# MCU.net
KiCad netlist of a schematic drawn in Altium Designer
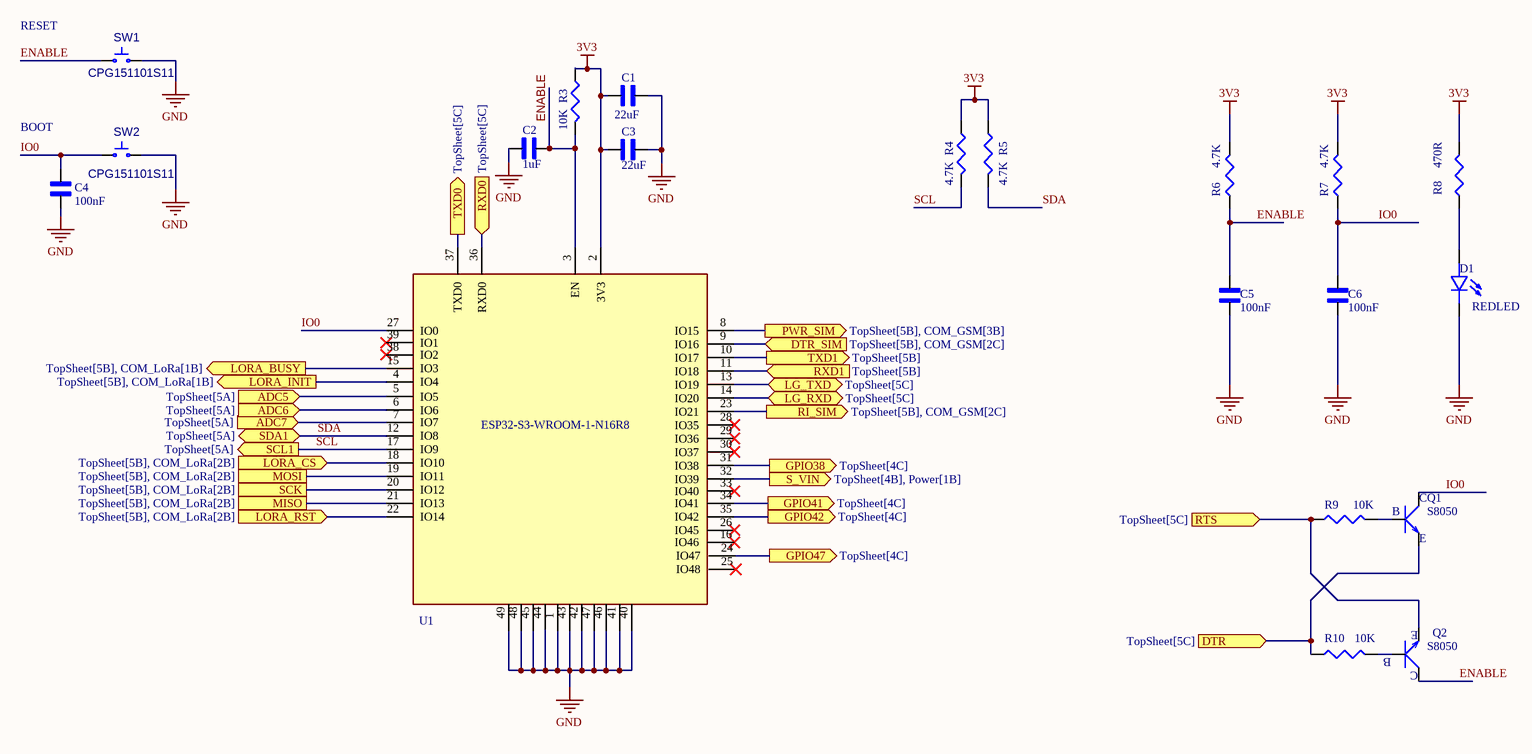
[diagram p0: MCU.SchDoc]

(export (version "E")
  (design (tool "Eeschema 10.0.6"))
  (components
    (comp (ref "C1")
      (value "22uF")
      (footprint "C0603")
      (fields (field (name "MF") "Murata") (field (name "MP") "GJM1555C1HR10BB01J"))
      (libsource (lib "") (part "Capacitor non polar_1"))
    )
    (comp (ref "C2")
      (value "1uF")
      (footprint "C0603")
      (fields (field (name "MF") "Murata") (field (name "MP") "GJM1555C1HR10BB01J"))
      (libsource (lib "") (part "Capacitor non polar_1"))
    )
    (comp (ref "C3")
      (value "22uF")
      (footprint "C0603")
      (fields (field (name "MF") "Murata") (field (name "MP") "GJM1555C1HR10BB01J"))
      (libsource (lib "") (part "Capacitor non polar_1"))
    )
    (comp (ref "C4")
      (value "100nF")
      (footprint "C0603")
      (fields (field (name "MF") "Murata") (field (name "MP") "GJM1555C1HR10BB01J"))
      (libsource (lib "") (part "Capacitor non polar_2"))
    )
    (comp (ref "C5")
      (value "100nF")
      (footprint "C0603")
      (fields (field (name "MF") "Murata") (field (name "MP") "GJM1555C1HR10BB01J"))
      (libsource (lib "common component") (part "Capacitor non polar"))
    )
    (comp (ref "C6")
      (value "100nF")
      (footprint "C0603")
      (fields (field (name "MF") "Murata") (field (name "MP") "GJM1555C1HR10BB01J"))
      (libsource (lib "common component") (part "Capacitor non polar"))
    )
    (comp (ref "D1")
      (value "REDLED")
      (footprint "0603D-B")
      (description "Generic LED SMD")
      (fields (field (name "MF") "Osram") (field (name "MP") "LHN974 RED LED 1206"))
      (libsource (lib "common component") (part "LED"))
    )
    (comp (ref "Q1")
      (value "S8050")
      (footprint "SOT95P237X112-3N")
      (description "Bipolar (BJT) Transistor NPN 25 V 500 mA 150MHz 300 mW Surface Mount SOT-23")
      (fields (field (name "MF") "UMW"))
      (libsource (lib "S8050") (part "S8050"))
    )
    (comp (ref "Q2")
      (value "S8050")
      (footprint "SOT95P237X112-3N")
      (description "Bipolar (BJT) Transistor NPN 25 V 500 mA 150MHz 300 mW Surface Mount SOT-23")
      (fields (field (name "MF") "UMW"))
      (libsource (lib "S8050") (part "S8050"))
    )
    (comp (ref "R3") (value "10K") (footprint "R0603") (libsource (lib "common component") (part "Resistor")))
    (comp (ref "R4")
      (value "4.7K")
      (footprint "R0603")
      (libsource (lib "common component") (part "Resistor"))
    )
    (comp (ref "R5")
      (value "4.7K")
      (footprint "R0603")
      (libsource (lib "common component") (part "Resistor"))
    )
    (comp (ref "R6")
      (value "4.7K")
      (footprint "R0603")
      (libsource (lib "common component") (part "Resistor"))
    )
    (comp (ref "R7")
      (value "4.7K")
      (footprint "R0603")
      (libsource (lib "common component") (part "Resistor"))
    )
    (comp (ref "R8")
      (value "470R")
      (footprint "R0603")
      (libsource (lib "common component") (part "Resistor"))
    )
    (comp (ref "R9") (value "10K") (footprint "R0603") (libsource (lib "common component") (part "Resistor")))
    (comp (ref "R10")
      (value "10K")
      (footprint "R0603")
      (libsource (lib "common component") (part "Resistor"))
    )
    (comp (ref "SW1")
      (value "CPG151101S11")
      (footprint "5.2 mm × 5.2 mm SW")
      (libsource (lib "common component") (part "Switch"))
    )
    (comp (ref "SW2")
      (value "CPG151101S11")
      (footprint "5.2 mm × 5.2 mm SW")
      (libsource (lib "common component") (part "Switch"))
    )
    (comp (ref "U1")
      (value "ESP32-S3-WROOM-1-N16R8")
      (footprint "ESP32S3WROOM1N8R2")
      (description "Bluetooth, WiFi 802.11b/g/n, Bluetooth v5.0 Transceiver Module 2.4GHz PCB Trace Surface Mount")
      (libsource (lib "ESP32-S3-WROOM-1-N16R8") (part "ESP32-S3-WROOM-1-N16R8"))
    )
  )
  (nets
    (net (code "1") (name "/ADC5") (class "Default")
      (node (ref "U1") (pin "5") (pinfunction "IO5_5") (pintype "passive"))
    )
    (net (code "2") (name "/ADC6") (class "Default")
      (node (ref "U1") (pin "6") (pinfunction "IO6_6") (pintype "passive"))
    )
    (net (code "3") (name "/ADC7") (class "Default")
      (node (ref "U1") (pin "7") (pinfunction "IO7_7") (pintype "passive"))
    )
    (net (code "4") (name "/DTR") (class "Default")
      (node (ref "Q1") (pin "2") (pinfunction "E_2") (pintype "passive"))
      (node (ref "R10") (pin "1") (pinfunction "1_1") (pintype "passive"))
    )
    (net (code "5") (name "/DTR_SIM") (class "Default")
      (node (ref "U1") (pin "9") (pinfunction "IO16_9") (pintype "passive"))
    )
    (net (code "6") (name "/ENABLE") (class "Default")
      (node (ref "C2") (pin "2") (pinfunction "2_2") (pintype "passive"))
      (node (ref "C5") (pin "1") (pinfunction "1_1") (pintype "passive"))
      (node (ref "Q2") (pin "3") (pinfunction "C_3") (pintype "passive"))
      (node (ref "R3") (pin "2") (pinfunction "2_2") (pintype "passive"))
      (node (ref "R6") (pin "1") (pinfunction "1_1") (pintype "passive"))
      (node (ref "SW1") (pin "1") (pinfunction "1_1") (pintype "passive"))
      (node (ref "U1") (pin "3") (pinfunction "EN_3") (pintype "passive"))
    )
    (net (code "7") (name "/GPIO38") (class "Default")
      (node (ref "U1") (pin "31") (pinfunction "IO38_31") (pintype "passive"))
    )
    (net (code "8") (name "/GPIO41") (class "Default")
      (node (ref "U1") (pin "34") (pinfunction "IO41_34") (pintype "passive"))
    )
    (net (code "9") (name "/GPIO42") (class "Default")
      (node (ref "U1") (pin "35") (pinfunction "IO42_35") (pintype "passive"))
    )
    (net (code "10") (name "/GPIO47") (class "Default")
      (node (ref "U1") (pin "24") (pinfunction "IO47_24") (pintype "passive"))
    )
    (net (code "11") (name "/IO0") (class "Default")
      (node (ref "C4") (pin "2") (pinfunction "2_2") (pintype "passive"))
      (node (ref "C6") (pin "1") (pinfunction "1_1") (pintype "passive"))
      (node (ref "Q1") (pin "3") (pinfunction "C_3") (pintype "passive"))
      (node (ref "R7") (pin "1") (pinfunction "1_1") (pintype "passive"))
      (node (ref "SW2") (pin "1") (pinfunction "1_1") (pintype "passive"))
      (node (ref "U1") (pin "27") (pinfunction "IO0_27") (pintype "passive"))
    )
    (net (code "12") (name "/LG_RXD") (class "Default")
      (node (ref "U1") (pin "14") (pinfunction "IO20_14") (pintype "passive"))
    )
    (net (code "13") (name "/LG_TXD") (class "Default")
      (node (ref "U1") (pin "13") (pinfunction "IO19_13") (pintype "passive"))
    )
    (net (code "14") (name "/LORA_BUSY") (class "Default")
      (node (ref "U1") (pin "15") (pinfunction "IO3_15") (pintype "passive"))
    )
    (net (code "15") (name "/LORA_CS") (class "Default")
      (node (ref "U1") (pin "18") (pinfunction "IO10_18") (pintype "passive"))
    )
    (net (code "16") (name "/LORA_INIT") (class "Default")
      (node (ref "U1") (pin "4") (pinfunction "IO4_4") (pintype "passive"))
    )
    (net (code "17") (name "/LORA_RST") (class "Default")
      (node (ref "U1") (pin "22") (pinfunction "IO14_22") (pintype "passive"))
    )
    (net (code "18") (name "/MISO") (class "Default")
      (node (ref "U1") (pin "21") (pinfunction "IO13_21") (pintype "passive"))
    )
    (net (code "19") (name "/MOSI") (class "Default")
      (node (ref "U1") (pin "19") (pinfunction "IO11_19") (pintype "passive"))
    )
    (net (code "20") (name "/PWR_SIM") (class "Default")
      (node (ref "U1") (pin "8") (pinfunction "IO15_8") (pintype "passive"))
    )
    (net (code "21") (name "/RI_SIM") (class "Default")
      (node (ref "U1") (pin "23") (pinfunction "IO21_23") (pintype "passive"))
    )
    (net (code "22") (name "/RTS") (class "Default")
      (node (ref "Q2") (pin "2") (pinfunction "E_2") (pintype "passive"))
      (node (ref "R9") (pin "1") (pinfunction "1_1") (pintype "passive"))
    )
    (net (code "23") (name "/RXD0") (class "Default")
      (node (ref "U1") (pin "36") (pinfunction "RXD0_36") (pintype "passive"))
    )
    (net (code "24") (name "/RXD1") (class "Default")
      (node (ref "U1") (pin "11") (pinfunction "IO18_11") (pintype "passive"))
    )
    (net (code "25") (name "/SCK") (class "Default")
      (node (ref "U1") (pin "20") (pinfunction "IO12_20") (pintype "passive"))
    )
    (net (code "26") (name "/SCL") (class "Default")
      (node (ref "R4") (pin "2") (pinfunction "2_2") (pintype "passive"))
      (node (ref "U1") (pin "17") (pinfunction "IO9_17") (pintype "passive"))
    )
    (net (code "27") (name "/SDA") (class "Default")
      (node (ref "R5") (pin "2") (pinfunction "2_2") (pintype "passive"))
      (node (ref "U1") (pin "12") (pinfunction "IO8_12") (pintype "passive"))
    )
    (net (code "28") (name "/S_VIN") (class "Default")
      (node (ref "U1") (pin "32") (pinfunction "IO39_32") (pintype "passive"))
    )
    (net (code "29") (name "/TXD0") (class "Default")
      (node (ref "U1") (pin "37") (pinfunction "TXD0_37") (pintype "passive"))
    )
    (net (code "30") (name "/TXD1") (class "Default")
      (node (ref "U1") (pin "10") (pinfunction "IO17_10") (pintype "passive"))
    )
    (net (code "31") (name "3V3") (class "Default")
      (node (ref "C1") (pin "1") (pinfunction "1_1") (pintype "passive"))
      (node (ref "C3") (pin "1") (pinfunction "1_1") (pintype "passive"))
      (node (ref "R3") (pin "1") (pinfunction "1_1") (pintype "passive"))
      (node (ref "R4") (pin "1") (pinfunction "1_1") (pintype "passive"))
      (node (ref "R5") (pin "1") (pinfunction "1_1") (pintype "passive"))
      (node (ref "R6") (pin "2") (pinfunction "2_2") (pintype "passive"))
      (node (ref "R7") (pin "2") (pinfunction "2_2") (pintype "passive"))
      (node (ref "R8") (pin "2") (pinfunction "2_2") (pintype "passive"))
      (node (ref "U1") (pin "2") (pinfunction "3V3_2") (pintype "passive"))
    )
    (net (code "32") (name "GND") (class "Default")
      (node (ref "C1") (pin "2") (pinfunction "2_2") (pintype "passive"))
      (node (ref "C2") (pin "1") (pinfunction "1_1") (pintype "passive"))
      (node (ref "C3") (pin "2") (pinfunction "2_2") (pintype "passive"))
      (node (ref "C4") (pin "1") (pinfunction "1_1") (pintype "passive"))
      (node (ref "C5") (pin "2") (pinfunction "2_2") (pintype "passive"))
      (node (ref "C6") (pin "2") (pinfunction "2_2") (pintype "passive"))
      (node (ref "D1") (pin "2") (pinfunction "NEG_2") (pintype "passive"))
      (node (ref "SW1") (pin "2") (pinfunction "2_2") (pintype "passive"))
      (node (ref "SW2") (pin "2") (pinfunction "2_2") (pintype "passive"))
    )
    (net (code "33") (name "Net-(D1-POS)") (class "Default")
      (node (ref "D1") (pin "1") (pinfunction "POS_1") (pintype "passive"))
      (node (ref "R8") (pin "1") (pinfunction "1_1") (pintype "passive"))
    )
    (net (code "34") (name "Net-(Q1-B)") (class "Default")
      (node (ref "Q1") (pin "1") (pinfunction "B_1") (pintype "passive"))
      (node (ref "R9") (pin "2") (pinfunction "2_2") (pintype "passive"))
    )
    (net (code "35") (name "Net-(Q2-B)") (class "Default")
      (node (ref "Q2") (pin "1") (pinfunction "B_1") (pintype "passive"))
      (node (ref "R10") (pin "2") (pinfunction "2_2") (pintype "passive"))
    )
    (net (code "36") (name "unconnected-(U1-GND-Pad1)") (class "Default")
      (node (ref "U1") (pin "1") (pinfunction "GND_1") (pintype "passive"))
    )
    (net (code "37") (name "unconnected-(U1-GND-Pad40)") (class "Default")
      (node (ref "U1") (pin "40") (pinfunction "GND_40") (pintype "passive"))
    )
    (net (code "38") (name "unconnected-(U1-GND-Pad41)") (class "Default")
      (node (ref "U1") (pin "41") (pinfunction "GND_41") (pintype "passive"))
    )
    (net (code "39") (name "unconnected-(U1-GND-Pad42)") (class "Default")
      (node (ref "U1") (pin "42") (pinfunction "GND_42") (pintype "passive"))
    )
    (net (code "40") (name "unconnected-(U1-GND-Pad43)") (class "Default")
      (node (ref "U1") (pin "43") (pinfunction "GND_43") (pintype "passive"))
    )
    (net (code "41") (name "unconnected-(U1-GND-Pad44)") (class "Default")
      (node (ref "U1") (pin "44") (pinfunction "GND_44") (pintype "passive"))
    )
    (net (code "42") (name "unconnected-(U1-GND-Pad45)") (class "Default")
      (node (ref "U1") (pin "45") (pinfunction "GND_45") (pintype "passive"))
    )
    (net (code "43") (name "unconnected-(U1-GND-Pad46)") (class "Default")
      (node (ref "U1") (pin "46") (pinfunction "GND_46") (pintype "passive"))
    )
    (net (code "44") (name "unconnected-(U1-GND-Pad47)") (class "Default")
      (node (ref "U1") (pin "47") (pinfunction "GND_47") (pintype "passive"))
    )
    (net (code "45") (name "unconnected-(U1-GND-Pad48)") (class "Default")
      (node (ref "U1") (pin "48") (pinfunction "GND_48") (pintype "passive"))
    )
    (net (code "46") (name "unconnected-(U1-GND-Pad49)") (class "Default")
      (node (ref "U1") (pin "49") (pinfunction "GND_49") (pintype "passive"))
    )
    (net (code "47") (name "unconnected-(U1-IO1-Pad39)") (class "Default")
      (node (ref "U1") (pin "39") (pinfunction "IO1_39") (pintype "passive+no_connect"))
    )
    (net (code "48") (name "unconnected-(U1-IO2-Pad38)") (class "Default")
      (node (ref "U1") (pin "38") (pinfunction "IO2_38") (pintype "passive+no_connect"))
    )
    (net (code "49") (name "unconnected-(U1-IO35-Pad28)") (class "Default")
      (node (ref "U1") (pin "28") (pinfunction "IO35_28") (pintype "passive+no_connect"))
    )
    (net (code "50") (name "unconnected-(U1-IO36-Pad29)") (class "Default")
      (node (ref "U1") (pin "29") (pinfunction "IO36_29") (pintype "passive+no_connect"))
    )
    (net (code "51") (name "unconnected-(U1-IO37-Pad30)") (class "Default")
      (node (ref "U1") (pin "30") (pinfunction "IO37_30") (pintype "passive+no_connect"))
    )
    (net (code "52") (name "unconnected-(U1-IO40-Pad33)") (class "Default")
      (node (ref "U1") (pin "33") (pinfunction "IO40_33") (pintype "passive+no_connect"))
    )
    (net (code "53") (name "unconnected-(U1-IO45-Pad26)") (class "Default")
      (node (ref "U1") (pin "26") (pinfunction "IO45_26") (pintype "passive+no_connect"))
    )
    (net (code "54") (name "unconnected-(U1-IO46-Pad16)") (class "Default")
      (node (ref "U1") (pin "16") (pinfunction "IO46_16") (pintype "passive+no_connect"))
    )
    (net (code "55") (name "unconnected-(U1-IO48-Pad25)") (class "Default")
      (node (ref "U1") (pin "25") (pinfunction "IO48_25") (pintype "passive+no_connect"))
    )
  )
)
